# mLRS-rx-board01-v013.net
KiCad netlist of a schematic drawn in EAGLE
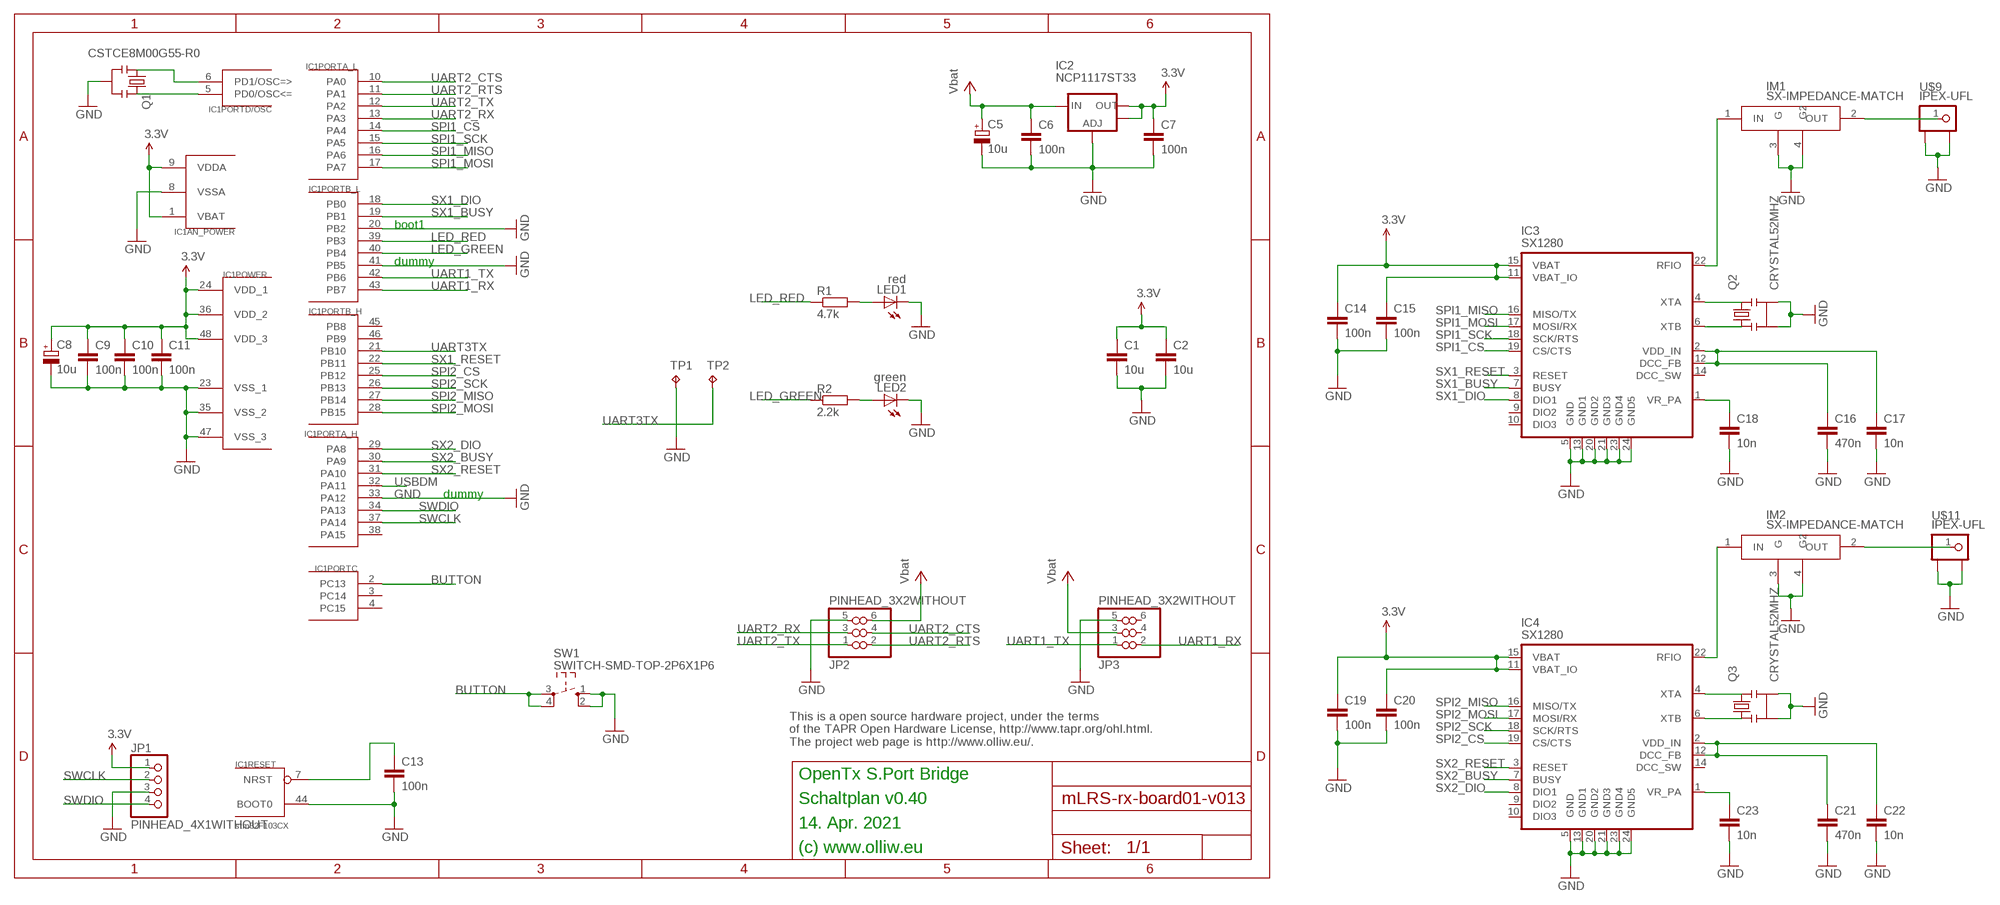
[diagram p0: schematic, sheet 1]

(export (version "E")
  (design (tool "Eeschema 10.0.6"))
  (components
    (comp (ref "C1")
      (value "10u")
      (footprint "eagle-import:C0603")
      (libsource (lib "eagle-import") (part "C-EUC0603"))
    )
    (comp (ref "C2")
      (value "10u")
      (footprint "eagle-import:C0603")
      (libsource (lib "eagle-import") (part "C-EUC0603"))
    )
    (comp (ref "C5")
      (value "10u")
      (footprint "eagle-import:SMC_A")
      (libsource (lib "eagle-import") (part "CPOL-EUSMCA"))
    )
    (comp (ref "C6")
      (value "100n")
      (footprint "eagle-import:C0603")
      (libsource (lib "eagle-import") (part "C-EUC0603"))
    )
    (comp (ref "C7")
      (value "100n")
      (footprint "eagle-import:C0603")
      (libsource (lib "eagle-import") (part "C-EUC0603"))
    )
    (comp (ref "C8")
      (value "10u")
      (footprint "eagle-import:SMC_A")
      (libsource (lib "eagle-import") (part "CPOL-EUSMCA"))
    )
    (comp (ref "C9")
      (value "100n")
      (footprint "eagle-import:C0603")
      (libsource (lib "eagle-import") (part "C-EUC0603"))
    )
    (comp (ref "C10")
      (value "100n")
      (footprint "eagle-import:C0603")
      (libsource (lib "eagle-import") (part "C-EUC0603"))
    )
    (comp (ref "C11")
      (value "100n")
      (footprint "eagle-import:C0603")
      (libsource (lib "eagle-import") (part "C-EUC0603"))
    )
    (comp (ref "C13")
      (value "100n")
      (footprint "eagle-import:C0603")
      (libsource (lib "eagle-import") (part "C-EUC0603"))
    )
    (comp (ref "C14")
      (value "100n")
      (footprint "eagle-import:C0402")
      (libsource (lib "eagle-import") (part "C-EUC0402"))
    )
    (comp (ref "C15")
      (value "100n")
      (footprint "eagle-import:C0402")
      (libsource (lib "eagle-import") (part "C-EUC0402"))
    )
    (comp (ref "C16")
      (value "470n")
      (footprint "eagle-import:C0402")
      (libsource (lib "eagle-import") (part "C-EUC0402"))
    )
    (comp (ref "C17")
      (value "10n")
      (footprint "eagle-import:C0402")
      (libsource (lib "eagle-import") (part "C-EUC0402"))
    )
    (comp (ref "C18")
      (value "10n")
      (footprint "eagle-import:C0402")
      (libsource (lib "eagle-import") (part "C-EUC0402"))
    )
    (comp (ref "C19")
      (value "100n")
      (footprint "eagle-import:C0402")
      (libsource (lib "eagle-import") (part "C-EUC0402"))
    )
    (comp (ref "C20")
      (value "100n")
      (footprint "eagle-import:C0402")
      (libsource (lib "eagle-import") (part "C-EUC0402"))
    )
    (comp (ref "C21")
      (value "470n")
      (footprint "eagle-import:C0402")
      (libsource (lib "eagle-import") (part "C-EUC0402"))
    )
    (comp (ref "C22")
      (value "10n")
      (footprint "eagle-import:C0402")
      (libsource (lib "eagle-import") (part "C-EUC0402"))
    )
    (comp (ref "C23")
      (value "10n")
      (footprint "eagle-import:C0402")
      (libsource (lib "eagle-import") (part "C-EUC0402"))
    )
    (comp (ref "IC1")
      (value "stm32F103CX")
      (footprint "eagle-import:TQFP48")
      (libsource (lib "eagle-import") (part "STM32F10XCXT6"))
    )
    (comp (ref "IC2")
      (value "NCP1117ST33")
      (footprint "eagle-import:SOT223")
      (libsource (lib "eagle-import") (part "V_REG_LM1117SOT223"))
    )
    (comp (ref "IC3")
      (value "SX1280")
      (footprint "eagle-import:QFN24-4X4-SX128X")
      (libsource (lib "eagle-import") (part "SX1280"))
    )
    (comp (ref "IC4")
      (value "SX1280")
      (footprint "eagle-import:QFN24-4X4-SX128X")
      (libsource (lib "eagle-import") (part "SX1280"))
    )
    (comp (ref "IM1")
      (value "SX-IMPEDANCE-MATCH")
      (footprint "eagle-import:SX-IMPEDANCE-MATCH")
      (libsource (lib "eagle-import") (part "SX-IMPEDANCE-MATCH"))
    )
    (comp (ref "IM2")
      (value "SX-IMPEDANCE-MATCH")
      (footprint "eagle-import:SX-IMPEDANCE-MATCH")
      (libsource (lib "eagle-import") (part "SX-IMPEDANCE-MATCH"))
    )
    (comp (ref "JP1")
      (value "PINHEAD_4X1WITHOUT")
      (footprint "eagle-import:PINHEAD_4X1_WO")
      (libsource (lib "eagle-import") (part "PINHEAD_4X1WITHOUT"))
    )
    (comp (ref "JP2")
      (value "PINHEAD_3X2WITHOUT")
      (footprint "eagle-import:PINHEAD_3X2_WO")
      (libsource (lib "eagle-import") (part "PINHEAD_3X2WITHOUT"))
    )
    (comp (ref "JP3")
      (value "PINHEAD_3X2WITHOUT")
      (footprint "eagle-import:PINHEAD_3X2_WO")
      (libsource (lib "eagle-import") (part "PINHEAD_3X2WITHOUT"))
    )
    (comp (ref "LED1")
      (value "red")
      (footprint "eagle-import:CHIPLED_0603")
      (libsource (lib "eagle-import") (part "LEDCHIPLED_0603"))
    )
    (comp (ref "LED2")
      (value "green")
      (footprint "eagle-import:CHIPLED_0603")
      (libsource (lib "eagle-import") (part "LEDCHIPLED_0603"))
    )
    (comp (ref "Q1")
      (value "CSTCE8M00G55-R0")
      (footprint "eagle-import:RESONATOR-SMD")
      (libsource (lib "eagle-import") (part "RESONATORSMD"))
    )
    (comp (ref "Q2")
      (value "CRYSTAL52MHZ")
      (footprint "eagle-import:CRYSTAL-SMD-2X1P6-GND")
      (libsource (lib "eagle-import") (part "CRYSTAL52MHZ"))
    )
    (comp (ref "Q3")
      (value "CRYSTAL52MHZ")
      (footprint "eagle-import:CRYSTAL-SMD-2X1P6-GND")
      (libsource (lib "eagle-import") (part "CRYSTAL52MHZ"))
    )
    (comp (ref "R1")
      (value "4.7k")
      (footprint "eagle-import:R0402")
      (libsource (lib "eagle-import") (part "R-EU_R0402"))
    )
    (comp (ref "R2")
      (value "2.2k")
      (footprint "eagle-import:R0402")
      (libsource (lib "eagle-import") (part "R-EU_R0402"))
    )
    (comp (ref "SW1")
      (value "SWITCH-SMD-TOP-2P6X1P6")
      (footprint "eagle-import:TACTILE-SWITCH-SMD-TOP-2P6X1X6")
      (libsource (lib "eagle-import") (part "SWITCH-SMD-TOP-2P6X1P6"))
    )
    (comp (ref "TP1")
      (value "TPB1,27")
      (footprint "eagle-import:B1,27")
      (libsource (lib "eagle-import") (part "TPB1,27"))
    )
    (comp (ref "TP2")
      (value "TPB1,27")
      (footprint "eagle-import:B1,27")
      (libsource (lib "eagle-import") (part "TPB1,27"))
    )
    (comp (ref "U$9")
      (value "IPEX-UFL")
      (footprint "eagle-import:IPEX-UFL-SMD")
      (libsource (lib "eagle-import") (part "IPEX-UFL"))
    )
    (comp (ref "U$11")
      (value "IPEX-UFL")
      (footprint "eagle-import:IPEX-UFL-SMD")
      (libsource (lib "eagle-import") (part "IPEX-UFL"))
    )
  )
  (nets
    (net (code "1") (name "/BUTTON") (class "Default")
      (node (ref "IC1") (pin "2") (pinfunction "PC13_2") (pintype "bidirectional"))
      (node (ref "SW1") (pin "3") (pinfunction "3_3") (pintype "passive"))
      (node (ref "SW1") (pin "4") (pinfunction "4_4") (pintype "passive"))
    )
    (net (code "2") (name "/LED_GREEN") (class "Default")
      (node (ref "IC1") (pin "40") (pinfunction "PB4_40") (pintype "bidirectional"))
      (node (ref "R2") (pin "1") (pinfunction "1_1") (pintype "passive"))
    )
    (net (code "3") (name "/LED_RED") (class "Default")
      (node (ref "IC1") (pin "39") (pinfunction "PB3_39") (pintype "bidirectional"))
      (node (ref "R1") (pin "1") (pinfunction "1_1") (pintype "passive"))
    )
    (net (code "4") (name "/SPI1_CS") (class "Default")
      (node (ref "IC1") (pin "14") (pinfunction "PA4_14") (pintype "bidirectional"))
      (node (ref "IC3") (pin "19") (pinfunction "CS/CTS_19") (pintype "input"))
    )
    (net (code "5") (name "/SPI1_MISO") (class "Default")
      (node (ref "IC1") (pin "16") (pinfunction "PA6_16") (pintype "bidirectional"))
      (node (ref "IC3") (pin "16") (pinfunction "MISO/TX_16") (pintype "input"))
    )
    (net (code "6") (name "/SPI1_MOSI") (class "Default")
      (node (ref "IC1") (pin "17") (pinfunction "PA7_17") (pintype "bidirectional"))
      (node (ref "IC3") (pin "17") (pinfunction "MOSI/RX_17") (pintype "input"))
    )
    (net (code "7") (name "/SPI1_SCK") (class "Default")
      (node (ref "IC1") (pin "15") (pinfunction "PA5_15") (pintype "bidirectional"))
      (node (ref "IC3") (pin "18") (pinfunction "SCK/RTS_18") (pintype "input"))
    )
    (net (code "8") (name "/SPI2_CS") (class "Default")
      (node (ref "IC1") (pin "25") (pinfunction "PB12_25") (pintype "bidirectional"))
      (node (ref "IC4") (pin "19") (pinfunction "CS/CTS_19") (pintype "input"))
    )
    (net (code "9") (name "/SPI2_MISO") (class "Default")
      (node (ref "IC1") (pin "27") (pinfunction "PB14_27") (pintype "bidirectional"))
      (node (ref "IC4") (pin "16") (pinfunction "MISO/TX_16") (pintype "input"))
    )
    (net (code "10") (name "/SPI2_MOSI") (class "Default")
      (node (ref "IC1") (pin "28") (pinfunction "PB15_28") (pintype "bidirectional"))
      (node (ref "IC4") (pin "17") (pinfunction "MOSI/RX_17") (pintype "input"))
    )
    (net (code "11") (name "/SPI2_SCK") (class "Default")
      (node (ref "IC1") (pin "26") (pinfunction "PB13_26") (pintype "bidirectional"))
      (node (ref "IC4") (pin "18") (pinfunction "SCK/RTS_18") (pintype "input"))
    )
    (net (code "12") (name "/SWCLK") (class "Default")
      (node (ref "IC1") (pin "37") (pinfunction "PA14_37") (pintype "bidirectional"))
      (node (ref "JP1") (pin "2") (pinfunction "2_2") (pintype "passive"))
    )
    (net (code "13") (name "/SWDIO") (class "Default")
      (node (ref "IC1") (pin "34") (pinfunction "PA13_34") (pintype "bidirectional"))
      (node (ref "JP1") (pin "4") (pinfunction "4_4") (pintype "passive"))
    )
    (net (code "14") (name "/SX1_BUSY") (class "Default")
      (node (ref "IC1") (pin "19") (pinfunction "PB1_19") (pintype "bidirectional"))
      (node (ref "IC3") (pin "7") (pinfunction "BUSY_7") (pintype "bidirectional"))
    )
    (net (code "15") (name "/SX1_DIO") (class "Default")
      (node (ref "IC1") (pin "18") (pinfunction "PB0_18") (pintype "bidirectional"))
      (node (ref "IC3") (pin "8") (pinfunction "DIO1_8") (pintype "input"))
    )
    (net (code "16") (name "/SX1_RESET") (class "Default")
      (node (ref "IC1") (pin "22") (pinfunction "PB11_22") (pintype "bidirectional"))
      (node (ref "IC3") (pin "3") (pinfunction "RESET_3") (pintype "bidirectional"))
    )
    (net (code "17") (name "/SX2_BUSY") (class "Default")
      (node (ref "IC1") (pin "30") (pinfunction "PA9_30") (pintype "bidirectional"))
      (node (ref "IC4") (pin "7") (pinfunction "BUSY_7") (pintype "bidirectional"))
    )
    (net (code "18") (name "/SX2_DIO") (class "Default")
      (node (ref "IC1") (pin "29") (pinfunction "PA8_29") (pintype "bidirectional"))
      (node (ref "IC4") (pin "8") (pinfunction "DIO1_8") (pintype "input"))
    )
    (net (code "19") (name "/SX2_RESET") (class "Default")
      (node (ref "IC1") (pin "31") (pinfunction "PA10_31") (pintype "bidirectional"))
      (node (ref "IC4") (pin "3") (pinfunction "RESET_3") (pintype "bidirectional"))
    )
    (net (code "20") (name "/UART1_RX") (class "Default")
      (node (ref "IC1") (pin "43") (pinfunction "PB7_43") (pintype "bidirectional"))
      (node (ref "JP3") (pin "2") (pinfunction "2_2") (pintype "passive"))
    )
    (net (code "21") (name "/UART1_TX") (class "Default")
      (node (ref "IC1") (pin "42") (pinfunction "PB6_42") (pintype "bidirectional"))
      (node (ref "JP3") (pin "1") (pinfunction "1_1") (pintype "passive"))
    )
    (net (code "22") (name "/UART2_CTS") (class "Default")
      (node (ref "IC1") (pin "10") (pinfunction "PA0_10") (pintype "bidirectional"))
      (node (ref "JP2") (pin "4") (pinfunction "4_4") (pintype "passive"))
    )
    (net (code "23") (name "/UART2_RTS") (class "Default")
      (node (ref "IC1") (pin "11") (pinfunction "PA1_11") (pintype "bidirectional"))
      (node (ref "JP2") (pin "2") (pinfunction "2_2") (pintype "passive"))
    )
    (net (code "24") (name "/UART2_RX") (class "Default")
      (node (ref "IC1") (pin "13") (pinfunction "PA3_13") (pintype "bidirectional"))
      (node (ref "JP2") (pin "3") (pinfunction "3_3") (pintype "passive"))
    )
    (net (code "25") (name "/UART2_TX") (class "Default")
      (node (ref "IC1") (pin "12") (pinfunction "PA2_12") (pintype "bidirectional"))
      (node (ref "JP2") (pin "1") (pinfunction "1_1") (pintype "passive"))
    )
    (net (code "26") (name "/UART3TX") (class "Default")
      (node (ref "IC1") (pin "21") (pinfunction "PB10_21") (pintype "bidirectional"))
      (node (ref "TP2") (pin "TP") (pinfunction "TP_TP") (pintype "input"))
    )
    (net (code "27") (name "/USBDM") (class "Default")
      (node (ref "IC1") (pin "32") (pinfunction "PA11_32") (pintype "bidirectional"))
    )
    (net (code "28") (name "3.3V") (class "Default")
      (node (ref "C1") (pin "1") (pinfunction "1_1") (pintype "passive"))
      (node (ref "C10") (pin "1") (pinfunction "1_1") (pintype "passive"))
      (node (ref "C11") (pin "1") (pinfunction "1_1") (pintype "passive"))
      (node (ref "C14") (pin "1") (pinfunction "1_1") (pintype "passive"))
      (node (ref "C15") (pin "1") (pinfunction "1_1") (pintype "passive"))
      (node (ref "C19") (pin "1") (pinfunction "1_1") (pintype "passive"))
      (node (ref "C2") (pin "1") (pinfunction "1_1") (pintype "passive"))
      (node (ref "C20") (pin "1") (pinfunction "1_1") (pintype "passive"))
      (node (ref "C7") (pin "1") (pinfunction "1_1") (pintype "passive"))
      (node (ref "C8") (pin "+") (pinfunction "+_+") (pintype "passive"))
      (node (ref "C9") (pin "1") (pinfunction "1_1") (pintype "passive"))
      (node (ref "IC1") (pin "1") (pinfunction "VBAT_1") (pintype "power_in"))
      (node (ref "IC1") (pin "24") (pinfunction "VDD_1_24") (pintype "power_in"))
      (node (ref "IC1") (pin "36") (pinfunction "VDD_2_36") (pintype "power_in"))
      (node (ref "IC1") (pin "48") (pinfunction "VDD_3_48") (pintype "power_in"))
      (node (ref "IC1") (pin "9") (pinfunction "VDDA_9") (pintype "power_in"))
      (node (ref "IC2") (pin "2") (pinfunction "OUT_2") (pintype "output"))
      (node (ref "IC2") (pin "4") (pinfunction "OUT_4") (pintype "output"))
      (node (ref "IC3") (pin "11") (pinfunction "VBAT_IO_11") (pintype "power_in"))
      (node (ref "IC3") (pin "15") (pinfunction "VBAT_15") (pintype "power_in"))
      (node (ref "IC4") (pin "11") (pinfunction "VBAT_IO_11") (pintype "power_in"))
      (node (ref "IC4") (pin "15") (pinfunction "VBAT_15") (pintype "power_in"))
      (node (ref "JP1") (pin "1") (pinfunction "1_1") (pintype "passive"))
    )
    (net (code "29") (name "GND") (class "Default")
      (node (ref "C1") (pin "2") (pinfunction "2_2") (pintype "passive"))
      (node (ref "C10") (pin "2") (pinfunction "2_2") (pintype "passive"))
      (node (ref "C11") (pin "2") (pinfunction "2_2") (pintype "passive"))
      (node (ref "C13") (pin "2") (pinfunction "2_2") (pintype "passive"))
      (node (ref "C14") (pin "2") (pinfunction "2_2") (pintype "passive"))
      (node (ref "C15") (pin "2") (pinfunction "2_2") (pintype "passive"))
      (node (ref "C16") (pin "2") (pinfunction "2_2") (pintype "passive"))
      (node (ref "C17") (pin "2") (pinfunction "2_2") (pintype "passive"))
      (node (ref "C18") (pin "2") (pinfunction "2_2") (pintype "passive"))
      (node (ref "C19") (pin "2") (pinfunction "2_2") (pintype "passive"))
      (node (ref "C2") (pin "2") (pinfunction "2_2") (pintype "passive"))
      (node (ref "C20") (pin "2") (pinfunction "2_2") (pintype "passive"))
      (node (ref "C21") (pin "2") (pinfunction "2_2") (pintype "passive"))
      (node (ref "C22") (pin "2") (pinfunction "2_2") (pintype "passive"))
      (node (ref "C23") (pin "2") (pinfunction "2_2") (pintype "passive"))
      (node (ref "C5") (pin "-") (pinfunction "-_-") (pintype "passive"))
      (node (ref "C6") (pin "2") (pinfunction "2_2") (pintype "passive"))
      (node (ref "C7") (pin "2") (pinfunction "2_2") (pintype "passive"))
      (node (ref "C8") (pin "-") (pinfunction "-_-") (pintype "passive"))
      (node (ref "C9") (pin "2") (pinfunction "2_2") (pintype "passive"))
      (node (ref "IC1") (pin "20") (pinfunction "PB2_20") (pintype "bidirectional"))
      (node (ref "IC1") (pin "23") (pinfunction "VSS_1_23") (pintype "power_in"))
      (node (ref "IC1") (pin "33") (pinfunction "PA12_33") (pintype "bidirectional"))
      (node (ref "IC1") (pin "35") (pinfunction "VSS_2_35") (pintype "power_in"))
      (node (ref "IC1") (pin "41") (pinfunction "PB5_41") (pintype "bidirectional"))
      (node (ref "IC1") (pin "44") (pinfunction "BOOT0_44") (pintype "input"))
      (node (ref "IC1") (pin "47") (pinfunction "VSS_3_47") (pintype "power_in"))
      (node (ref "IC1") (pin "8") (pinfunction "VSSA_8") (pintype "power_in"))
      (node (ref "IC2") (pin "1") (pinfunction "ADJ_1") (pintype "input"))
      (node (ref "IC3") (pin "13") (pinfunction "GND1_13") (pintype "power_in"))
      (node (ref "IC3") (pin "20") (pinfunction "GND2_20") (pintype "power_in"))
      (node (ref "IC3") (pin "21") (pinfunction "GND3_21") (pintype "power_in"))
      (node (ref "IC3") (pin "23") (pinfunction "GND4_23") (pintype "power_in"))
      (node (ref "IC3") (pin "24") (pinfunction "GND5_24") (pintype "power_in"))
      (node (ref "IC3") (pin "5") (pinfunction "GND_5") (pintype "power_in"))
      (node (ref "IC4") (pin "13") (pinfunction "GND1_13") (pintype "power_in"))
      (node (ref "IC4") (pin "20") (pinfunction "GND2_20") (pintype "power_in"))
      (node (ref "IC4") (pin "21") (pinfunction "GND3_21") (pintype "power_in"))
      (node (ref "IC4") (pin "23") (pinfunction "GND4_23") (pintype "power_in"))
      (node (ref "IC4") (pin "24") (pinfunction "GND5_24") (pintype "power_in"))
      (node (ref "IC4") (pin "5") (pinfunction "GND_5") (pintype "power_in"))
      (node (ref "IM1") (pin "3") (pinfunction "G_3") (pintype "power_in"))
      (node (ref "IM1") (pin "4") (pinfunction "G2_4") (pintype "power_in"))
      (node (ref "IM2") (pin "3") (pinfunction "G_3") (pintype "power_in"))
      (node (ref "IM2") (pin "4") (pinfunction "G2_4") (pintype "power_in"))
      (node (ref "JP1") (pin "3") (pinfunction "3_3") (pintype "passive"))
      (node (ref "JP2") (pin "5") (pinfunction "5_5") (pintype "passive"))
      (node (ref "JP3") (pin "5") (pinfunction "5_5") (pintype "passive"))
      (node (ref "LED1") (pin "C") (pinfunction "C_C") (pintype "passive"))
      (node (ref "LED2") (pin "C") (pinfunction "C_C") (pintype "passive"))
      (node (ref "Q1") (pin "2") (pinfunction "2_2") (pintype "passive"))
      (node (ref "Q2") (pin "2") (pinfunction "2_2") (pintype "passive"))
      (node (ref "Q2") (pin "4") (pinfunction "4_4") (pintype "passive"))
      (node (ref "Q3") (pin "2") (pinfunction "2_2") (pintype "passive"))
      (node (ref "Q3") (pin "4") (pinfunction "4_4") (pintype "passive"))
      (node (ref "SW1") (pin "1") (pinfunction "1_1") (pintype "passive"))
      (node (ref "SW1") (pin "2") (pinfunction "2_2") (pintype "passive"))
      (node (ref "TP1") (pin "TP") (pinfunction "TP_TP") (pintype "input"))
      (node (ref "U$11") (pin "2") (pinfunction "2_2") (pintype "power_in"))
      (node (ref "U$11") (pin "3") (pinfunction "3_3") (pintype "power_in"))
      (node (ref "U$9") (pin "2") (pinfunction "2_2") (pintype "power_in"))
      (node (ref "U$9") (pin "3") (pinfunction "3_3") (pintype "power_in"))
    )
    (net (code "30") (name "Net-(IC1G-PD0{slash}OSC<=)") (class "Default")
      (node (ref "IC1") (pin "5") (pinfunction "PD0/OSC<=_5") (pintype "bidirectional"))
      (node (ref "Q1") (pin "3") (pinfunction "3_3") (pintype "passive"))
    )
    (net (code "31") (name "Net-(IC1G-PD1{slash}OSC=>)") (class "Default")
      (node (ref "IC1") (pin "6") (pinfunction "PD1/OSC=>_6") (pintype "bidirectional"))
      (node (ref "Q1") (pin "1") (pinfunction "1_1") (pintype "passive"))
    )
    (net (code "32") (name "Net-(IC1I-NRST)") (class "Default")
      (node (ref "C13") (pin "1") (pinfunction "1_1") (pintype "passive"))
      (node (ref "IC1") (pin "7") (pinfunction "NRST_7") (pintype "input"))
    )
    (net (code "33") (name "Net-(IC3-DCC_FB)") (class "Default")
      (node (ref "C16") (pin "1") (pinfunction "1_1") (pintype "passive"))
      (node (ref "C17") (pin "1") (pinfunction "1_1") (pintype "passive"))
      (node (ref "IC3") (pin "12") (pinfunction "DCC_FB_12") (pintype "bidirectional"))
      (node (ref "IC3") (pin "2") (pinfunction "VDD_IN_2") (pintype "power_in"))
    )
    (net (code "34") (name "Net-(IC3-RFIO)") (class "Default")
      (node (ref "IC3") (pin "22") (pinfunction "RFIO_22") (pintype "bidirectional"))
      (node (ref "IM1") (pin "1") (pinfunction "IN_1") (pintype "bidirectional"))
    )
    (net (code "35") (name "Net-(IC3-VR_PA)") (class "Default")
      (node (ref "C18") (pin "1") (pinfunction "1_1") (pintype "passive"))
      (node (ref "IC3") (pin "1") (pinfunction "VR_PA_1") (pintype "bidirectional"))
    )
    (net (code "36") (name "Net-(IC3-XTA)") (class "Default")
      (node (ref "IC3") (pin "4") (pinfunction "XTA_4") (pintype "bidirectional"))
      (node (ref "Q2") (pin "3") (pinfunction "3_3") (pintype "passive"))
    )
    (net (code "37") (name "Net-(IC3-XTB)") (class "Default")
      (node (ref "IC3") (pin "6") (pinfunction "XTB_6") (pintype "bidirectional"))
      (node (ref "Q2") (pin "1") (pinfunction "1_1") (pintype "passive"))
    )
    (net (code "38") (name "Net-(IC4-DCC_FB)") (class "Default")
      (node (ref "C21") (pin "1") (pinfunction "1_1") (pintype "passive"))
      (node (ref "C22") (pin "1") (pinfunction "1_1") (pintype "passive"))
      (node (ref "IC4") (pin "12") (pinfunction "DCC_FB_12") (pintype "bidirectional"))
      (node (ref "IC4") (pin "2") (pinfunction "VDD_IN_2") (pintype "power_in"))
    )
    (net (code "39") (name "Net-(IC4-RFIO)") (class "Default")
      (node (ref "IC4") (pin "22") (pinfunction "RFIO_22") (pintype "bidirectional"))
      (node (ref "IM2") (pin "1") (pinfunction "IN_1") (pintype "bidirectional"))
    )
    (net (code "40") (name "Net-(IC4-VR_PA)") (class "Default")
      (node (ref "C23") (pin "1") (pinfunction "1_1") (pintype "passive"))
      (node (ref "IC4") (pin "1") (pinfunction "VR_PA_1") (pintype "bidirectional"))
    )
    (net (code "41") (name "Net-(IC4-XTA)") (class "Default")
      (node (ref "IC4") (pin "4") (pinfunction "XTA_4") (pintype "bidirectional"))
      (node (ref "Q3") (pin "3") (pinfunction "3_3") (pintype "passive"))
    )
    (net (code "42") (name "Net-(IC4-XTB)") (class "Default")
      (node (ref "IC4") (pin "6") (pinfunction "XTB_6") (pintype "bidirectional"))
      (node (ref "Q3") (pin "1") (pinfunction "1_1") (pintype "passive"))
    )
    (net (code "43") (name "Net-(IM1-OUT)") (class "Default")
      (node (ref "IM1") (pin "2") (pinfunction "OUT_2") (pintype "bidirectional"))
      (node (ref "U$9") (pin "1") (pinfunction "1_1") (pintype "passive"))
    )
    (net (code "44") (name "Net-(IM2-OUT)") (class "Default")
      (node (ref "IM2") (pin "2") (pinfunction "OUT_2") (pintype "bidirectional"))
      (node (ref "U$11") (pin "1") (pinfunction "1_1") (pintype "passive"))
    )
    (net (code "45") (name "Net-(LED1-PadA)") (class "Default")
      (node (ref "LED1") (pin "A") (pinfunction "A_A") (pintype "passive"))
      (node (ref "R1") (pin "2") (pinfunction "2_2") (pintype "passive"))
    )
    (net (code "46") (name "Net-(LED2-PadA)") (class "Default")
      (node (ref "LED2") (pin "A") (pinfunction "A_A") (pintype "passive"))
      (node (ref "R2") (pin "2") (pinfunction "2_2") (pintype "passive"))
    )
    (net (code "47") (name "Vbat") (class "Default")
      (node (ref "C5") (pin "+") (pinfunction "+_+") (pintype "passive"))
      (node (ref "C6") (pin "1") (pinfunction "1_1") (pintype "passive"))
      (node (ref "IC2") (pin "3") (pinfunction "IN_3") (pintype "input"))
      (node (ref "JP2") (pin "6") (pinfunction "6_6") (pintype "passive"))
      (node (ref "JP3") (pin "3") (pinfunction "3_3") (pintype "passive"))
    )
    (net (code "48") (name "unconnected-(IC1B-PA15-Pad38)") (class "Default")
      (node (ref "IC1") (pin "38") (pinfunction "PA15_38") (pintype "bidirectional"))
    )
    (net (code "49") (name "unconnected-(IC1D-PB8-Pad45)") (class "Default")
      (node (ref "IC1") (pin "45") (pinfunction "PB8_45") (pintype "bidirectional"))
    )
    (net (code "50") (name "unconnected-(IC1D-PB9-Pad46)") (class "Default")
      (node (ref "IC1") (pin "46") (pinfunction "PB9_46") (pintype "bidirectional"))
    )
    (net (code "51") (name "unconnected-(IC1F-PC14-Pad3)") (class "Default")
      (node (ref "IC1") (pin "3") (pinfunction "PC14_3") (pintype "bidirectional"))
    )
    (net (code "52") (name "unconnected-(IC1F-PC15-Pad4)") (class "Default")
      (node (ref "IC1") (pin "4") (pinfunction "PC15_4") (pintype "bidirectional"))
    )
    (net (code "53") (name "unconnected-(IC3-DCC_SW-Pad14)") (class "Default")
      (node (ref "IC3") (pin "14") (pinfunction "DCC_SW_14") (pintype "bidirectional"))
    )
    (net (code "54") (name "unconnected-(IC3-DIO2-Pad9)") (class "Default")
      (node (ref "IC3") (pin "9") (pinfunction "DIO2_9") (pintype "input"))
    )
    (net (code "55") (name "unconnected-(IC3-DIO3-Pad10)") (class "Default")
      (node (ref "IC3") (pin "10") (pinfunction "DIO3_10") (pintype "input"))
    )
    (net (code "56") (name "unconnected-(IC4-DCC_SW-Pad14)") (class "Default")
      (node (ref "IC4") (pin "14") (pinfunction "DCC_SW_14") (pintype "bidirectional"))
    )
    (net (code "57") (name "unconnected-(IC4-DIO2-Pad9)") (class "Default")
      (node (ref "IC4") (pin "9") (pinfunction "DIO2_9") (pintype "input"))
    )
    (net (code "58") (name "unconnected-(IC4-DIO3-Pad10)") (class "Default")
      (node (ref "IC4") (pin "10") (pinfunction "DIO3_10") (pintype "input"))
    )
    (net (code "59") (name "unconnected-(JP3-Pad4)") (class "Default")
      (node (ref "JP3") (pin "4") (pinfunction "4_4") (pintype "passive"))
    )
    (net (code "60") (name "unconnected-(JP3-Pad6)") (class "Default")
      (node (ref "JP3") (pin "6") (pinfunction "6_6") (pintype "passive"))
    )
  )
)
